# SparkFun_ProtoShield_Kit_rev32.net
KiCad netlist of a schematic drawn in EAGLE
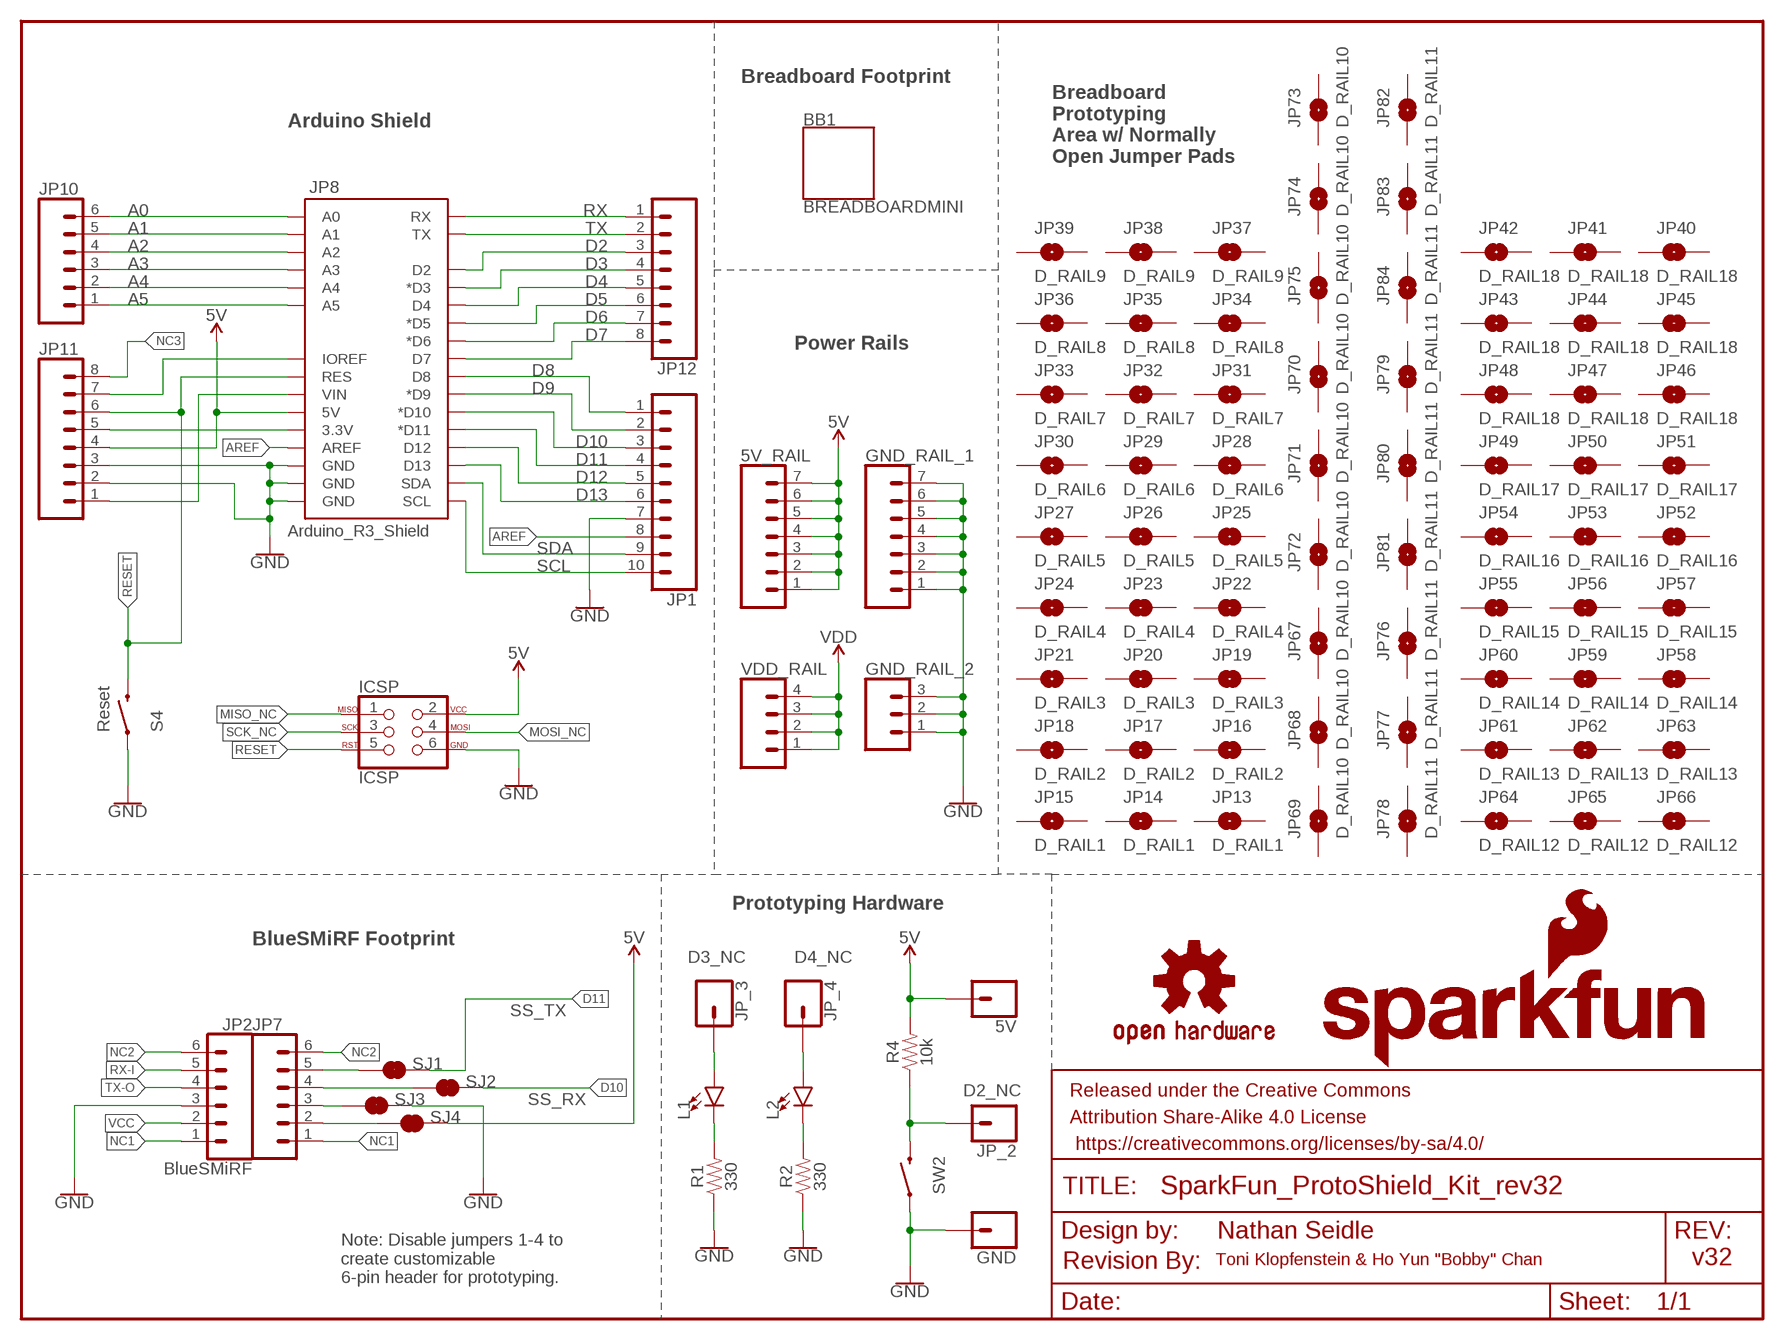
[diagram p0: schematic, sheet 1]

(export (version "E")
  (design (tool "Eeschema 10.0.6"))
  (components
    (comp (ref "5V")
      (value "CONN_01")
      (footprint "eagle-import:1X01")
      (libsource (lib "eagle-import") (part "CONN_01"))
    )
    (comp (ref "5V_RAIL")
      (value "CONN_07NO_SILK")
      (footprint "eagle-import:1X07_NO_SILK")
      (libsource (lib "eagle-import") (part "CONN_07NO_SILK"))
    )
    (comp (ref "BB1")
      (value "BREADBOARDMINI")
      (footprint "eagle-import:BREADBOARD-MINI")
      (libsource (lib "eagle-import") (part "BREADBOARDMINI"))
    )
    (comp (ref "FRAME1")
      (value "FRAME-LETTER")
      (footprint "eagle-import:CREATIVE_COMMONS")
      (libsource (lib "eagle-import") (part "FRAME-LETTER"))
    )
    (comp (ref "GND")
      (value "CONN_01")
      (footprint "eagle-import:1X01")
      (libsource (lib "eagle-import") (part "CONN_01"))
    )
    (comp (ref "GND_RAIL_1")
      (value "CONN_07NO_SILK")
      (footprint "eagle-import:1X07_NO_SILK")
      (libsource (lib "eagle-import") (part "CONN_07NO_SILK"))
    )
    (comp (ref "GND_RAIL_2")
      (value "CONN_031X03_NO_SILK")
      (footprint "eagle-import:1X03_NO_SILK")
      (libsource (lib "eagle-import") (part "CONN_031X03_NO_SILK"))
    )
    (comp (ref "ICSP")
      (value "ICSP")
      (footprint "eagle-import:2X3")
      (libsource (lib "eagle-import") (part "AVR_SPI_PROG_3X2PTH"))
    )
    (comp (ref "JP1")
      (value "CONN_10\"")
      (footprint "eagle-import:1X10")
      (libsource (lib "eagle-import") (part "CONN_10{dblquote}"))
    )
    (comp (ref "JP2")
      (value "BlueSMiRF")
      (footprint "eagle-import:1X06")
      (libsource (lib "eagle-import") (part "CONN_06SILK_FEMALE_PTH"))
    )
    (comp (ref "JP7")
      (value "CONN_06SILK_FEMALE_PTH")
      (footprint "eagle-import:1X06")
      (libsource (lib "eagle-import") (part "CONN_06SILK_FEMALE_PTH"))
    )
    (comp (ref "JP8")
      (value "ARDUINO_R3_SHIELDR3_PROTO_SHIELD")
      (footprint "eagle-import:UNO_R3_PROTO_SHIELD")
      (libsource (lib "eagle-import") (part "ARDUINO_R3_SHIELDR3_PROTO_SHIELD"))
    )
    (comp (ref "JP10")
      (value "CONN_06SILK_FEMALE_PTH")
      (footprint "eagle-import:1X06")
      (libsource (lib "eagle-import") (part "CONN_06SILK_FEMALE_PTH"))
    )
    (comp (ref "JP11")
      (value "CONN_08\"")
      (footprint "eagle-import:1X08")
      (libsource (lib "eagle-import") (part "CONN_08{dblquote}"))
    )
    (comp (ref "JP12")
      (value "CONN_08\"")
      (footprint "eagle-import:1X08")
      (libsource (lib "eagle-import") (part "CONN_08{dblquote}"))
    )
    (comp (ref "JP13")
      (value "D_RAIL1")
      (footprint "eagle-import:SMT-JUMPER_2_NO_NO-SILK")
      (libsource (lib "eagle-import") (part "JUMPER-SMT_2_NO_NO-SILK"))
    )
    (comp (ref "JP14")
      (value "D_RAIL1")
      (footprint "eagle-import:SMT-JUMPER_2_NO_NO-SILK")
      (libsource (lib "eagle-import") (part "JUMPER-SMT_2_NO_NO-SILK"))
    )
    (comp (ref "JP15")
      (value "D_RAIL1")
      (footprint "eagle-import:SMT-JUMPER_2_NO_NO-SILK")
      (libsource (lib "eagle-import") (part "JUMPER-SMT_2_NO_NO-SILK"))
    )
    (comp (ref "JP16")
      (value "D_RAIL2")
      (footprint "eagle-import:SMT-JUMPER_2_NO_NO-SILK")
      (libsource (lib "eagle-import") (part "JUMPER-SMT_2_NO_NO-SILK"))
    )
    (comp (ref "JP17")
      (value "D_RAIL2")
      (footprint "eagle-import:SMT-JUMPER_2_NO_NO-SILK")
      (libsource (lib "eagle-import") (part "JUMPER-SMT_2_NO_NO-SILK"))
    )
    (comp (ref "JP18")
      (value "D_RAIL2")
      (footprint "eagle-import:SMT-JUMPER_2_NO_NO-SILK")
      (libsource (lib "eagle-import") (part "JUMPER-SMT_2_NO_NO-SILK"))
    )
    (comp (ref "JP19")
      (value "D_RAIL3")
      (footprint "eagle-import:SMT-JUMPER_2_NO_NO-SILK")
      (libsource (lib "eagle-import") (part "JUMPER-SMT_2_NO_NO-SILK"))
    )
    (comp (ref "JP20")
      (value "D_RAIL3")
      (footprint "eagle-import:SMT-JUMPER_2_NO_NO-SILK")
      (libsource (lib "eagle-import") (part "JUMPER-SMT_2_NO_NO-SILK"))
    )
    (comp (ref "JP21")
      (value "D_RAIL3")
      (footprint "eagle-import:SMT-JUMPER_2_NO_NO-SILK")
      (libsource (lib "eagle-import") (part "JUMPER-SMT_2_NO_NO-SILK"))
    )
    (comp (ref "JP22")
      (value "D_RAIL4")
      (footprint "eagle-import:SMT-JUMPER_2_NO_NO-SILK")
      (libsource (lib "eagle-import") (part "JUMPER-SMT_2_NO_NO-SILK"))
    )
    (comp (ref "JP23")
      (value "D_RAIL4")
      (footprint "eagle-import:SMT-JUMPER_2_NO_NO-SILK")
      (libsource (lib "eagle-import") (part "JUMPER-SMT_2_NO_NO-SILK"))
    )
    (comp (ref "JP24")
      (value "D_RAIL4")
      (footprint "eagle-import:SMT-JUMPER_2_NO_NO-SILK")
      (libsource (lib "eagle-import") (part "JUMPER-SMT_2_NO_NO-SILK"))
    )
    (comp (ref "JP25")
      (value "D_RAIL5")
      (footprint "eagle-import:SMT-JUMPER_2_NO_NO-SILK")
      (libsource (lib "eagle-import") (part "JUMPER-SMT_2_NO_NO-SILK"))
    )
    (comp (ref "JP26")
      (value "D_RAIL5")
      (footprint "eagle-import:SMT-JUMPER_2_NO_NO-SILK")
      (libsource (lib "eagle-import") (part "JUMPER-SMT_2_NO_NO-SILK"))
    )
    (comp (ref "JP27")
      (value "D_RAIL5")
      (footprint "eagle-import:SMT-JUMPER_2_NO_NO-SILK")
      (libsource (lib "eagle-import") (part "JUMPER-SMT_2_NO_NO-SILK"))
    )
    (comp (ref "JP28")
      (value "D_RAIL6")
      (footprint "eagle-import:SMT-JUMPER_2_NO_NO-SILK")
      (libsource (lib "eagle-import") (part "JUMPER-SMT_2_NO_NO-SILK"))
    )
    (comp (ref "JP29")
      (value "D_RAIL6")
      (footprint "eagle-import:SMT-JUMPER_2_NO_NO-SILK")
      (libsource (lib "eagle-import") (part "JUMPER-SMT_2_NO_NO-SILK"))
    )
    (comp (ref "JP30")
      (value "D_RAIL6")
      (footprint "eagle-import:SMT-JUMPER_2_NO_NO-SILK")
      (libsource (lib "eagle-import") (part "JUMPER-SMT_2_NO_NO-SILK"))
    )
    (comp (ref "JP31")
      (value "D_RAIL7")
      (footprint "eagle-import:SMT-JUMPER_2_NO_NO-SILK")
      (libsource (lib "eagle-import") (part "JUMPER-SMT_2_NO_NO-SILK"))
    )
    (comp (ref "JP32")
      (value "D_RAIL7")
      (footprint "eagle-import:SMT-JUMPER_2_NO_NO-SILK")
      (libsource (lib "eagle-import") (part "JUMPER-SMT_2_NO_NO-SILK"))
    )
    (comp (ref "JP33")
      (value "D_RAIL7")
      (footprint "eagle-import:SMT-JUMPER_2_NO_NO-SILK")
      (libsource (lib "eagle-import") (part "JUMPER-SMT_2_NO_NO-SILK"))
    )
    (comp (ref "JP34")
      (value "D_RAIL8")
      (footprint "eagle-import:SMT-JUMPER_2_NO_NO-SILK")
      (libsource (lib "eagle-import") (part "JUMPER-SMT_2_NO_NO-SILK"))
    )
    (comp (ref "JP35")
      (value "D_RAIL8")
      (footprint "eagle-import:SMT-JUMPER_2_NO_NO-SILK")
      (libsource (lib "eagle-import") (part "JUMPER-SMT_2_NO_NO-SILK"))
    )
    (comp (ref "JP36")
      (value "D_RAIL8")
      (footprint "eagle-import:SMT-JUMPER_2_NO_NO-SILK")
      (libsource (lib "eagle-import") (part "JUMPER-SMT_2_NO_NO-SILK"))
    )
    (comp (ref "JP37")
      (value "D_RAIL9")
      (footprint "eagle-import:SMT-JUMPER_2_NO_NO-SILK")
      (libsource (lib "eagle-import") (part "JUMPER-SMT_2_NO_NO-SILK"))
    )
    (comp (ref "JP38")
      (value "D_RAIL9")
      (footprint "eagle-import:SMT-JUMPER_2_NO_NO-SILK")
      (libsource (lib "eagle-import") (part "JUMPER-SMT_2_NO_NO-SILK"))
    )
    (comp (ref "JP39")
      (value "D_RAIL9")
      (footprint "eagle-import:SMT-JUMPER_2_NO_NO-SILK")
      (libsource (lib "eagle-import") (part "JUMPER-SMT_2_NO_NO-SILK"))
    )
    (comp (ref "JP40")
      (value "D_RAIL18")
      (footprint "eagle-import:SMT-JUMPER_2_NO_NO-SILK")
      (libsource (lib "eagle-import") (part "JUMPER-SMT_2_NO_NO-SILK"))
    )
    (comp (ref "JP41")
      (value "D_RAIL18")
      (footprint "eagle-import:SMT-JUMPER_2_NO_NO-SILK")
      (libsource (lib "eagle-import") (part "JUMPER-SMT_2_NO_NO-SILK"))
    )
    (comp (ref "JP42")
      (value "D_RAIL18")
      (footprint "eagle-import:SMT-JUMPER_2_NO_NO-SILK")
      (libsource (lib "eagle-import") (part "JUMPER-SMT_2_NO_NO-SILK"))
    )
    (comp (ref "JP43")
      (value "D_RAIL18")
      (footprint "eagle-import:SMT-JUMPER_2_NO_NO-SILK")
      (libsource (lib "eagle-import") (part "JUMPER-SMT_2_NO_NO-SILK"))
    )
    (comp (ref "JP44")
      (value "D_RAIL18")
      (footprint "eagle-import:SMT-JUMPER_2_NO_NO-SILK")
      (libsource (lib "eagle-import") (part "JUMPER-SMT_2_NO_NO-SILK"))
    )
    (comp (ref "JP45")
      (value "D_RAIL18")
      (footprint "eagle-import:SMT-JUMPER_2_NO_NO-SILK")
      (libsource (lib "eagle-import") (part "JUMPER-SMT_2_NO_NO-SILK"))
    )
    (comp (ref "JP46")
      (value "D_RAIL18")
      (footprint "eagle-import:SMT-JUMPER_2_NO_NO-SILK")
      (libsource (lib "eagle-import") (part "JUMPER-SMT_2_NO_NO-SILK"))
    )
    (comp (ref "JP47")
      (value "D_RAIL18")
      (footprint "eagle-import:SMT-JUMPER_2_NO_NO-SILK")
      (libsource (lib "eagle-import") (part "JUMPER-SMT_2_NO_NO-SILK"))
    )
    (comp (ref "JP48")
      (value "D_RAIL18")
      (footprint "eagle-import:SMT-JUMPER_2_NO_NO-SILK")
      (libsource (lib "eagle-import") (part "JUMPER-SMT_2_NO_NO-SILK"))
    )
    (comp (ref "JP49")
      (value "D_RAIL17")
      (footprint "eagle-import:SMT-JUMPER_2_NO_NO-SILK")
      (libsource (lib "eagle-import") (part "JUMPER-SMT_2_NO_NO-SILK"))
    )
    (comp (ref "JP50")
      (value "D_RAIL17")
      (footprint "eagle-import:SMT-JUMPER_2_NO_NO-SILK")
      (libsource (lib "eagle-import") (part "JUMPER-SMT_2_NO_NO-SILK"))
    )
    (comp (ref "JP51")
      (value "D_RAIL17")
      (footprint "eagle-import:SMT-JUMPER_2_NO_NO-SILK")
      (libsource (lib "eagle-import") (part "JUMPER-SMT_2_NO_NO-SILK"))
    )
    (comp (ref "JP52")
      (value "D_RAIL16")
      (footprint "eagle-import:SMT-JUMPER_2_NO_NO-SILK")
      (libsource (lib "eagle-import") (part "JUMPER-SMT_2_NO_NO-SILK"))
    )
    (comp (ref "JP53")
      (value "D_RAIL16")
      (footprint "eagle-import:SMT-JUMPER_2_NO_NO-SILK")
      (libsource (lib "eagle-import") (part "JUMPER-SMT_2_NO_NO-SILK"))
    )
    (comp (ref "JP54")
      (value "D_RAIL16")
      (footprint "eagle-import:SMT-JUMPER_2_NO_NO-SILK")
      (libsource (lib "eagle-import") (part "JUMPER-SMT_2_NO_NO-SILK"))
    )
    (comp (ref "JP55")
      (value "D_RAIL15")
      (footprint "eagle-import:SMT-JUMPER_2_NO_NO-SILK")
      (libsource (lib "eagle-import") (part "JUMPER-SMT_2_NO_NO-SILK"))
    )
    (comp (ref "JP56")
      (value "D_RAIL15")
      (footprint "eagle-import:SMT-JUMPER_2_NO_NO-SILK")
      (libsource (lib "eagle-import") (part "JUMPER-SMT_2_NO_NO-SILK"))
    )
    (comp (ref "JP57")
      (value "D_RAIL15")
      (footprint "eagle-import:SMT-JUMPER_2_NO_NO-SILK")
      (libsource (lib "eagle-import") (part "JUMPER-SMT_2_NO_NO-SILK"))
    )
    (comp (ref "JP58")
      (value "D_RAIL14")
      (footprint "eagle-import:SMT-JUMPER_2_NO_NO-SILK")
      (libsource (lib "eagle-import") (part "JUMPER-SMT_2_NO_NO-SILK"))
    )
    (comp (ref "JP59")
      (value "D_RAIL14")
      (footprint "eagle-import:SMT-JUMPER_2_NO_NO-SILK")
      (libsource (lib "eagle-import") (part "JUMPER-SMT_2_NO_NO-SILK"))
    )
    (comp (ref "JP60")
      (value "D_RAIL14")
      (footprint "eagle-import:SMT-JUMPER_2_NO_NO-SILK")
      (libsource (lib "eagle-import") (part "JUMPER-SMT_2_NO_NO-SILK"))
    )
    (comp (ref "JP61")
      (value "D_RAIL13")
      (footprint "eagle-import:SMT-JUMPER_2_NO_NO-SILK")
      (libsource (lib "eagle-import") (part "JUMPER-SMT_2_NO_NO-SILK"))
    )
    (comp (ref "JP62")
      (value "D_RAIL13")
      (footprint "eagle-import:SMT-JUMPER_2_NO_NO-SILK")
      (libsource (lib "eagle-import") (part "JUMPER-SMT_2_NO_NO-SILK"))
    )
    (comp (ref "JP63")
      (value "D_RAIL13")
      (footprint "eagle-import:SMT-JUMPER_2_NO_NO-SILK")
      (libsource (lib "eagle-import") (part "JUMPER-SMT_2_NO_NO-SILK"))
    )
    (comp (ref "JP64")
      (value "D_RAIL12")
      (footprint "eagle-import:SMT-JUMPER_2_NO_NO-SILK")
      (libsource (lib "eagle-import") (part "JUMPER-SMT_2_NO_NO-SILK"))
    )
    (comp (ref "JP65")
      (value "D_RAIL12")
      (footprint "eagle-import:SMT-JUMPER_2_NO_NO-SILK")
      (libsource (lib "eagle-import") (part "JUMPER-SMT_2_NO_NO-SILK"))
    )
    (comp (ref "JP66")
      (value "D_RAIL12")
      (footprint "eagle-import:SMT-JUMPER_2_NO_NO-SILK")
      (libsource (lib "eagle-import") (part "JUMPER-SMT_2_NO_NO-SILK"))
    )
    (comp (ref "JP67")
      (value "D_RAIL10")
      (footprint "eagle-import:SMT-JUMPER_2_NO_NO-SILK")
      (libsource (lib "eagle-import") (part "JUMPER-SMT_2_NO_NO-SILK"))
    )
    (comp (ref "JP68")
      (value "D_RAIL10")
      (footprint "eagle-import:SMT-JUMPER_2_NO_NO-SILK")
      (libsource (lib "eagle-import") (part "JUMPER-SMT_2_NO_NO-SILK"))
    )
    (comp (ref "JP69")
      (value "D_RAIL10")
      (footprint "eagle-import:SMT-JUMPER_2_NO_NO-SILK")
      (libsource (lib "eagle-import") (part "JUMPER-SMT_2_NO_NO-SILK"))
    )
    (comp (ref "JP70")
      (value "D_RAIL10")
      (footprint "eagle-import:SMT-JUMPER_2_NO_NO-SILK")
      (libsource (lib "eagle-import") (part "JUMPER-SMT_2_NO_NO-SILK"))
    )
    (comp (ref "JP71")
      (value "D_RAIL10")
      (footprint "eagle-import:SMT-JUMPER_2_NO_NO-SILK")
      (libsource (lib "eagle-import") (part "JUMPER-SMT_2_NO_NO-SILK"))
    )
    (comp (ref "JP72")
      (value "D_RAIL10")
      (footprint "eagle-import:SMT-JUMPER_2_NO_NO-SILK")
      (libsource (lib "eagle-import") (part "JUMPER-SMT_2_NO_NO-SILK"))
    )
    (comp (ref "JP73")
      (value "D_RAIL10")
      (footprint "eagle-import:SMT-JUMPER_2_NO_NO-SILK")
      (libsource (lib "eagle-import") (part "JUMPER-SMT_2_NO_NO-SILK"))
    )
    (comp (ref "JP74")
      (value "D_RAIL10")
      (footprint "eagle-import:SMT-JUMPER_2_NO_NO-SILK")
      (libsource (lib "eagle-import") (part "JUMPER-SMT_2_NO_NO-SILK"))
    )
    (comp (ref "JP75")
      (value "D_RAIL10")
      (footprint "eagle-import:SMT-JUMPER_2_NO_NO-SILK")
      (libsource (lib "eagle-import") (part "JUMPER-SMT_2_NO_NO-SILK"))
    )
    (comp (ref "JP76")
      (value "D_RAIL11")
      (footprint "eagle-import:SMT-JUMPER_2_NO_NO-SILK")
      (libsource (lib "eagle-import") (part "JUMPER-SMT_2_NO_NO-SILK"))
    )
    (comp (ref "JP77")
      (value "D_RAIL11")
      (footprint "eagle-import:SMT-JUMPER_2_NO_NO-SILK")
      (libsource (lib "eagle-import") (part "JUMPER-SMT_2_NO_NO-SILK"))
    )
    (comp (ref "JP78")
      (value "D_RAIL11")
      (footprint "eagle-import:SMT-JUMPER_2_NO_NO-SILK")
      (libsource (lib "eagle-import") (part "JUMPER-SMT_2_NO_NO-SILK"))
    )
    (comp (ref "JP79")
      (value "D_RAIL11")
      (footprint "eagle-import:SMT-JUMPER_2_NO_NO-SILK")
      (libsource (lib "eagle-import") (part "JUMPER-SMT_2_NO_NO-SILK"))
    )
    (comp (ref "JP80")
      (value "D_RAIL11")
      (footprint "eagle-import:SMT-JUMPER_2_NO_NO-SILK")
      (libsource (lib "eagle-import") (part "JUMPER-SMT_2_NO_NO-SILK"))
    )
    (comp (ref "JP81")
      (value "D_RAIL11")
      (footprint "eagle-import:SMT-JUMPER_2_NO_NO-SILK")
      (libsource (lib "eagle-import") (part "JUMPER-SMT_2_NO_NO-SILK"))
    )
    (comp (ref "JP82")
      (value "D_RAIL11")
      (footprint "eagle-import:SMT-JUMPER_2_NO_NO-SILK")
      (libsource (lib "eagle-import") (part "JUMPER-SMT_2_NO_NO-SILK"))
    )
    (comp (ref "JP83")
      (value "D_RAIL11")
      (footprint "eagle-import:SMT-JUMPER_2_NO_NO-SILK")
      (libsource (lib "eagle-import") (part "JUMPER-SMT_2_NO_NO-SILK"))
    )
    (comp (ref "JP84")
      (value "D_RAIL11")
      (footprint "eagle-import:SMT-JUMPER_2_NO_NO-SILK")
      (libsource (lib "eagle-import") (part "JUMPER-SMT_2_NO_NO-SILK"))
    )
    (comp (ref "JP_2")
      (value "CONN_01")
      (footprint "eagle-import:1X01")
      (libsource (lib "eagle-import") (part "CONN_01"))
    )
    (comp (ref "JP_3")
      (value "CONN_01")
      (footprint "eagle-import:1X01")
      (libsource (lib "eagle-import") (part "CONN_01"))
    )
    (comp (ref "JP_4")
      (value "CONN_01")
      (footprint "eagle-import:1X01")
      (libsource (lib "eagle-import") (part "CONN_01"))
    )
    (comp (ref "L1")
      (value "LED3MM")
      (footprint "eagle-import:LED_3MM")
      (libsource (lib "eagle-import") (part "LED3MM"))
    )
    (comp (ref "L2")
      (value "LED3MM")
      (footprint "eagle-import:LED_3MM")
      (libsource (lib "eagle-import") (part "LED3MM"))
    )
    (comp (ref "LOGO1")
      (value "OSHW-LOGOS")
      (footprint "eagle-import:OSHW-LOGO-S")
      (libsource (lib "eagle-import") (part "OSHW-LOGOS"))
    )
    (comp (ref "R1")
      (value "330")
      (footprint "eagle-import:AXIAL-0.3")
      (libsource (lib "eagle-import") (part "330OHM-HORIZ-1/10W-5%"))
    )
    (comp (ref "R2")
      (value "330")
      (footprint "eagle-import:AXIAL-0.3")
      (libsource (lib "eagle-import") (part "330OHM-HORIZ-1/10W-5%"))
    )
    (comp (ref "R4")
      (value "10k")
      (footprint "eagle-import:AXIAL-0.3")
      (libsource (lib "eagle-import") (part "10KOHM-HORIZ-1/4W-5%"))
    )
    (comp (ref "S4")
      (value "MOMENTARY-SWITCH-SPST-PTH-6.0MM")
      (footprint "eagle-import:TACTILE_SWITCH_PTH_6.0MM")
      (libsource (lib "eagle-import") (part "MOMENTARY-SWITCH-SPST-PTH-6.0MM"))
    )
    (comp (ref "SJ1")
      (value "JUMPER-SMT_2_NC_TRACE_SILK")
      (footprint "eagle-import:SMT-JUMPER_2_NC_TRACE_SILK")
      (libsource (lib "eagle-import") (part "JUMPER-SMT_2_NC_TRACE_SILK"))
    )
    (comp (ref "SJ2")
      (value "JUMPER-SMT_2_NC_TRACE_SILK")
      (footprint "eagle-import:SMT-JUMPER_2_NC_TRACE_SILK")
      (libsource (lib "eagle-import") (part "JUMPER-SMT_2_NC_TRACE_SILK"))
    )
    (comp (ref "SJ3")
      (value "JUMPER-SMT_2_NC_TRACE_SILK")
      (footprint "eagle-import:SMT-JUMPER_2_NC_TRACE_SILK")
      (libsource (lib "eagle-import") (part "JUMPER-SMT_2_NC_TRACE_SILK"))
    )
    (comp (ref "SJ4")
      (value "JUMPER-SMT_2_NC_TRACE_SILK")
      (footprint "eagle-import:SMT-JUMPER_2_NC_TRACE_SILK")
      (libsource (lib "eagle-import") (part "JUMPER-SMT_2_NC_TRACE_SILK"))
    )
    (comp (ref "SW2")
      (value "MOMENTARY-SWITCH-SPST-PTH-6.0MM")
      (footprint "eagle-import:TACTILE_SWITCH_PTH_6.0MM")
      (libsource (lib "eagle-import") (part "MOMENTARY-SWITCH-SPST-PTH-6.0MM"))
    )
    (comp (ref "U$1")
      (value "SFE_LOGO_NAME_FLAME.1_INCH")
      (footprint "eagle-import:SFE_LOGO_NAME_FLAME_.1")
      (libsource (lib "eagle-import") (part "SFE_LOGO_NAME_FLAME.1_INCH"))
    )
    (comp (ref "U$2")
      (value "REVISION")
      (footprint "eagle-import:REVISION")
      (libsource (lib "eagle-import") (part "REVISION"))
    )
    (comp (ref "VDD_RAIL")
      (value "CONN_041X04_NO_SILK")
      (footprint "eagle-import:1X04_NO_SILK")
      (libsource (lib "eagle-import") (part "CONN_041X04_NO_SILK"))
    )
  )
  (nets
    (net (code "1") (name "/D2") (class "Default")
      (node (ref "JP12") (pin "3") (pinfunction "3_3") (pintype "passive"))
      (node (ref "JP8") (pin "D2") (pinfunction "D2_D2") (pintype "bidirectional"))
    )
    (net (code "2") (name "/D2_NC") (class "Default")
      (node (ref "JP_2") (pin "1") (pinfunction "1_1") (pintype "passive"))
      (node (ref "R4") (pin "P$1") (pinfunction "1_P$1") (pintype "passive"))
      (node (ref "SW2") (pin "3") (pinfunction "2_3") (pintype "passive"))
    )
    (net (code "3") (name "/D3") (class "Default")
      (node (ref "JP12") (pin "4") (pinfunction "4_4") (pintype "passive"))
      (node (ref "JP8") (pin "D3") (pinfunction "*D3_D3") (pintype "bidirectional"))
    )
    (net (code "4") (name "/D4") (class "Default")
      (node (ref "JP12") (pin "5") (pinfunction "5_5") (pintype "passive"))
      (node (ref "JP8") (pin "D4") (pinfunction "D4_D4") (pintype "bidirectional"))
    )
    (net (code "5") (name "/D5") (class "Default")
      (node (ref "JP12") (pin "6") (pinfunction "6_6") (pintype "passive"))
      (node (ref "JP8") (pin "D5") (pinfunction "*D5_D5") (pintype "bidirectional"))
    )
    (net (code "6") (name "/D6") (class "Default")
      (node (ref "JP12") (pin "7") (pinfunction "7_7") (pintype "passive"))
      (node (ref "JP8") (pin "D6") (pinfunction "*D6_D6") (pintype "bidirectional"))
    )
    (net (code "7") (name "/D7") (class "Default")
      (node (ref "JP12") (pin "8") (pinfunction "8_8") (pintype "passive"))
      (node (ref "JP8") (pin "D7") (pinfunction "D7_D7") (pintype "bidirectional"))
    )
    (net (code "8") (name "/D8") (class "Default")
      (node (ref "JP1") (pin "1") (pinfunction "1_1") (pintype "passive"))
      (node (ref "JP8") (pin "D8") (pinfunction "D8_D8") (pintype "bidirectional"))
    )
    (net (code "9") (name "/D9") (class "Default")
      (node (ref "JP1") (pin "2") (pinfunction "2_2") (pintype "passive"))
      (node (ref "JP8") (pin "D9") (pinfunction "*D9_D9") (pintype "bidirectional"))
    )
    (net (code "10") (name "/D12") (class "Default")
      (node (ref "JP1") (pin "5") (pinfunction "5_5") (pintype "passive"))
      (node (ref "JP8") (pin "D12") (pinfunction "D12_D12") (pintype "bidirectional"))
    )
    (net (code "11") (name "/D13") (class "Default")
      (node (ref "JP1") (pin "6") (pinfunction "6_6") (pintype "passive"))
      (node (ref "JP8") (pin "D13") (pinfunction "D13_D13") (pintype "bidirectional"))
    )
    (net (code "12") (name "/RX") (class "Default")
      (node (ref "JP12") (pin "1") (pinfunction "1_1") (pintype "passive"))
      (node (ref "JP8") (pin "RX") (pinfunction "RX_RX") (pintype "bidirectional"))
    )
    (net (code "13") (name "/SCL") (class "Default")
      (node (ref "JP1") (pin "10") (pinfunction "10_10") (pintype "passive"))
      (node (ref "JP8") (pin "SCL") (pinfunction "SCL_SCL") (pintype "bidirectional"))
    )
    (net (code "14") (name "/SDA") (class "Default")
      (node (ref "JP1") (pin "9") (pinfunction "9_9") (pintype "passive"))
      (node (ref "JP8") (pin "SDA") (pinfunction "SDA_SDA") (pintype "bidirectional"))
    )
    (net (code "15") (name "/TX") (class "Default")
      (node (ref "JP12") (pin "2") (pinfunction "2_2") (pintype "passive"))
      (node (ref "JP8") (pin "TX") (pinfunction "TX_TX") (pintype "bidirectional"))
    )
    (net (code "16") (name "5V") (class "Default")
      (node (ref "5V") (pin "1") (pinfunction "1_1") (pintype "passive"))
      (node (ref "5V_RAIL") (pin "1") (pinfunction "1_1") (pintype "passive"))
      (node (ref "5V_RAIL") (pin "2") (pinfunction "2_2") (pintype "passive"))
      (node (ref "5V_RAIL") (pin "3") (pinfunction "3_3") (pintype "passive"))
      (node (ref "5V_RAIL") (pin "4") (pinfunction "4_4") (pintype "passive"))
      (node (ref "5V_RAIL") (pin "5") (pinfunction "5_5") (pintype "passive"))
      (node (ref "5V_RAIL") (pin "6") (pinfunction "6_6") (pintype "passive"))
      (node (ref "5V_RAIL") (pin "7") (pinfunction "7_7") (pintype "passive"))
      (node (ref "ICSP") (pin "2") (pinfunction "2_2") (pintype "passive"))
      (node (ref "JP11") (pin "4") (pinfunction "4_4") (pintype "passive"))
      (node (ref "JP8") (pin "5V") (pinfunction "5V_5V") (pintype "bidirectional"))
      (node (ref "R4") (pin "P$2") (pinfunction "2_P$2") (pintype "passive"))
      (node (ref "SJ4") (pin "2") (pinfunction "2_2") (pintype "passive"))
    )
    (net (code "17") (name "AREF") (class "Default")
      (node (ref "JP1") (pin "8") (pinfunction "8_8") (pintype "passive"))
      (node (ref "JP8") (pin "AREF") (pinfunction "AREF_AREF") (pintype "bidirectional"))
    )
    (net (code "18") (name "D10") (class "Default")
      (node (ref "JP1") (pin "3") (pinfunction "3_3") (pintype "passive"))
      (node (ref "JP8") (pin "D10") (pinfunction "*D10_D10") (pintype "bidirectional"))
      (node (ref "SJ2") (pin "2") (pinfunction "2_2") (pintype "passive"))
    )
    (net (code "19") (name "D11") (class "Default")
      (node (ref "JP1") (pin "4") (pinfunction "4_4") (pintype "passive"))
      (node (ref "JP8") (pin "D11") (pinfunction "*D11_D11") (pintype "bidirectional"))
      (node (ref "SJ1") (pin "2") (pinfunction "2_2") (pintype "passive"))
    )
    (net (code "20") (name "GND") (class "Default")
      (node (ref "GND") (pin "1") (pinfunction "1_1") (pintype "passive"))
      (node (ref "GND_RAIL_1") (pin "1") (pinfunction "1_1") (pintype "passive"))
      (node (ref "GND_RAIL_1") (pin "2") (pinfunction "2_2") (pintype "passive"))
      (node (ref "GND_RAIL_1") (pin "3") (pinfunction "3_3") (pintype "passive"))
      (node (ref "GND_RAIL_1") (pin "4") (pinfunction "4_4") (pintype "passive"))
      (node (ref "GND_RAIL_1") (pin "5") (pinfunction "5_5") (pintype "passive"))
      (node (ref "GND_RAIL_1") (pin "6") (pinfunction "6_6") (pintype "passive"))
      (node (ref "GND_RAIL_1") (pin "7") (pinfunction "7_7") (pintype "passive"))
      (node (ref "GND_RAIL_2") (pin "1") (pinfunction "1_1") (pintype "passive"))
      (node (ref "GND_RAIL_2") (pin "2") (pinfunction "2_2") (pintype "passive"))
      (node (ref "GND_RAIL_2") (pin "3") (pinfunction "3_3") (pintype "passive"))
      (node (ref "ICSP") (pin "6") (pinfunction "6_6") (pintype "passive"))
      (node (ref "JP1") (pin "7") (pinfunction "7_7") (pintype "passive"))
      (node (ref "JP11") (pin "2") (pinfunction "2_2") (pintype "passive"))
      (node (ref "JP11") (pin "3") (pinfunction "3_3") (pintype "passive"))
      (node (ref "JP2") (pin "3") (pinfunction "3_3") (pintype "passive"))
      (node (ref "JP7") (pin "3") (pinfunction "3_3") (pintype "passive"))
      (node (ref "JP8") (pin "GND@0") (pinfunction "GND_GND@0") (pintype "bidirectional"))
      (node (ref "JP8") (pin "GND@1") (pinfunction "GND_GND@1") (pintype "bidirectional"))
      (node (ref "JP8") (pin "GND@2") (pinfunction "GND_GND@2") (pintype "bidirectional"))
      (node (ref "R1") (pin "P$1") (pinfunction "1_P$1") (pintype "passive"))
      (node (ref "R2") (pin "P$1") (pinfunction "1_P$1") (pintype "passive"))
      (node (ref "S4") (pin "1") (pinfunction "1_1") (pintype "passive"))
      (node (ref "SJ3") (pin "1") (pinfunction "1_1") (pintype "passive"))
      (node (ref "SJ3") (pin "2") (pinfunction "2_2") (pintype "passive"))
      (node (ref "SW2") (pin "1") (pinfunction "1_1") (pintype "passive"))
    )
    (net (code "21") (name "MISO_NC") (class "Default")
      (node (ref "ICSP") (pin "1") (pinfunction "1_1") (pintype "passive"))
    )
    (net (code "22") (name "MOSI_NC") (class "Default")
      (node (ref "ICSP") (pin "4") (pinfunction "4_4") (pintype "passive"))
    )
    (net (code "23") (name "NC1") (class "Default")
      (node (ref "JP2") (pin "1") (pinfunction "1_1") (pintype "passive"))
      (node (ref "JP7") (pin "1") (pinfunction "1_1") (pintype "passive"))
    )
    (net (code "24") (name "NC2") (class "Default")
      (node (ref "JP2") (pin "6") (pinfunction "6_6") (pintype "passive"))
      (node (ref "JP7") (pin "6") (pinfunction "6_6") (pintype "passive"))
    )
    (net (code "25") (name "NC3") (class "Default")
      (node (ref "JP11") (pin "8") (pinfunction "8_8") (pintype "passive"))
    )
    (net (code "26") (name "Net-(JP10-Pad1)") (class "Default")
      (node (ref "JP10") (pin "1") (pinfunction "1_1") (pintype "passive"))
      (node (ref "JP8") (pin "A5") (pinfunction "A5_A5") (pintype "bidirectional"))
    )
    (net (code "27") (name "Net-(JP10-Pad2)") (class "Default")
      (node (ref "JP10") (pin "2") (pinfunction "2_2") (pintype "passive"))
      (node (ref "JP8") (pin "A4") (pinfunction "A4_A4") (pintype "bidirectional"))
    )
    (net (code "28") (name "Net-(JP10-Pad3)") (class "Default")
      (node (ref "JP10") (pin "3") (pinfunction "3_3") (pintype "passive"))
      (node (ref "JP8") (pin "A3") (pinfunction "A3_A3") (pintype "bidirectional"))
    )
    (net (code "29") (name "Net-(JP10-Pad4)") (class "Default")
      (node (ref "JP10") (pin "4") (pinfunction "4_4") (pintype "passive"))
      (node (ref "JP8") (pin "A2") (pinfunction "A2_A2") (pintype "bidirectional"))
    )
    (net (code "30") (name "Net-(JP10-Pad5)") (class "Default")
      (node (ref "JP10") (pin "5") (pinfunction "5_5") (pintype "passive"))
      (node (ref "JP8") (pin "A1") (pinfunction "A1_A1") (pintype "bidirectional"))
    )
    (net (code "31") (name "Net-(JP10-Pad6)") (class "Default")
      (node (ref "JP10") (pin "6") (pinfunction "6_6") (pintype "passive"))
      (node (ref "JP8") (pin "A0") (pinfunction "A0_A0") (pintype "bidirectional"))
    )
    (net (code "32") (name "Net-(JP11-Pad1)") (class "Default")
      (node (ref "JP11") (pin "1") (pinfunction "1_1") (pintype "passive"))
      (node (ref "JP8") (pin "VIN") (pinfunction "VIN_VIN") (pintype "bidirectional"))
    )
    (net (code "33") (name "Net-(JP11-Pad5)") (class "Default")
      (node (ref "JP11") (pin "5") (pinfunction "5_5") (pintype "passive"))
      (node (ref "JP8") (pin "3.3V") (pinfunction "3.3V_3.3V") (pintype "bidirectional"))
    )
    (net (code "34") (name "Net-(JP11-Pad7)") (class "Default")
      (node (ref "JP11") (pin "7") (pinfunction "7_7") (pintype "passive"))
      (node (ref "JP8") (pin "IOREF") (pinfunction "IOREF_IOREF") (pintype "bidirectional"))
    )
    (net (code "35") (name "Net-(JP_3-Pad1)") (class "Default")
      (node (ref "JP_3") (pin "1") (pinfunction "1_1") (pintype "passive"))
      (node (ref "L1") (pin "A") (pinfunction "A_A") (pintype "passive"))
    )
    (net (code "36") (name "Net-(JP_4-Pad1)") (class "Default")
      (node (ref "JP_4") (pin "1") (pinfunction "1_1") (pintype "passive"))
      (node (ref "L2") (pin "A") (pinfunction "A_A") (pintype "passive"))
    )
    (net (code "37") (name "Net-(L1-C)") (class "Default")
      (node (ref "L1") (pin "K") (pinfunction "C_K") (pintype "passive"))
      (node (ref "R1") (pin "P$2") (pinfunction "2_P$2") (pintype "passive"))
    )
    (net (code "38") (name "Net-(L2-C)") (class "Default")
      (node (ref "L2") (pin "K") (pinfunction "C_K") (pintype "passive"))
      (node (ref "R2") (pin "P$2") (pinfunction "2_P$2") (pintype "passive"))
    )
    (net (code "39") (name "RESET") (class "Default")
      (node (ref "ICSP") (pin "5") (pinfunction "5_5") (pintype "passive"))
      (node (ref "JP11") (pin "6") (pinfunction "6_6") (pintype "passive"))
      (node (ref "JP8") (pin "RES") (pinfunction "RES_RES") (pintype "bidirectional"))
      (node (ref "S4") (pin "3") (pinfunction "2_3") (pintype "passive"))
    )
    (net (code "40") (name "RX-I") (class "Default")
      (node (ref "JP2") (pin "5") (pinfunction "5_5") (pintype "passive"))
      (node (ref "JP7") (pin "5") (pinfunction "5_5") (pintype "passive"))
      (node (ref "SJ1") (pin "1") (pinfunction "1_1") (pintype "passive"))
    )
    (net (code "41") (name "SCK_NC") (class "Default")
      (node (ref "ICSP") (pin "3") (pinfunction "3_3") (pintype "passive"))
    )
    (net (code "42") (name "TX-O") (class "Default")
      (node (ref "JP2") (pin "4") (pinfunction "4_4") (pintype "passive"))
      (node (ref "JP7") (pin "4") (pinfunction "4_4") (pintype "passive"))
      (node (ref "SJ2") (pin "1") (pinfunction "1_1") (pintype "passive"))
    )
    (net (code "43") (name "VCC") (class "Default")
      (node (ref "JP2") (pin "2") (pinfunction "2_2") (pintype "passive"))
      (node (ref "JP7") (pin "2") (pinfunction "2_2") (pintype "passive"))
      (node (ref "SJ4") (pin "1") (pinfunction "1_1") (pintype "passive"))
    )
    (net (code "44") (name "VDD") (class "Default")
      (node (ref "VDD_RAIL") (pin "1") (pinfunction "1_1") (pintype "passive"))
      (node (ref "VDD_RAIL") (pin "2") (pinfunction "2_2") (pintype "passive"))
      (node (ref "VDD_RAIL") (pin "3") (pinfunction "3_3") (pintype "passive"))
      (node (ref "VDD_RAIL") (pin "4") (pinfunction "4_4") (pintype "passive"))
    )
    (net (code "45") (name "unconnected-(JP13-Pad1)") (class "Default")
      (node (ref "JP13") (pin "1") (pinfunction "1_1") (pintype "passive"))
    )
    (net (code "46") (name "unconnected-(JP13-Pad2)") (class "Default")
      (node (ref "JP13") (pin "2") (pinfunction "2_2") (pintype "passive"))
    )
    (net (code "47") (name "unconnected-(JP14-Pad1)") (class "Default")
      (node (ref "JP14") (pin "1") (pinfunction "1_1") (pintype "passive"))
    )
    (net (code "48") (name "unconnected-(JP14-Pad2)") (class "Default")
      (node (ref "JP14") (pin "2") (pinfunction "2_2") (pintype "passive"))
    )
    (net (code "49") (name "unconnected-(JP15-Pad1)") (class "Default")
      (node (ref "JP15") (pin "1") (pinfunction "1_1") (pintype "passive"))
    )
    (net (code "50") (name "unconnected-(JP15-Pad2)") (class "Default")
      (node (ref "JP15") (pin "2") (pinfunction "2_2") (pintype "passive"))
    )
    (net (code "51") (name "unconnected-(JP16-Pad1)") (class "Default")
      (node (ref "JP16") (pin "1") (pinfunction "1_1") (pintype "passive"))
    )
    (net (code "52") (name "unconnected-(JP16-Pad2)") (class "Default")
      (node (ref "JP16") (pin "2") (pinfunction "2_2") (pintype "passive"))
    )
    (net (code "53") (name "unconnected-(JP17-Pad1)") (class "Default")
      (node (ref "JP17") (pin "1") (pinfunction "1_1") (pintype "passive"))
    )
    (net (code "54") (name "unconnected-(JP17-Pad2)") (class "Default")
      (node (ref "JP17") (pin "2") (pinfunction "2_2") (pintype "passive"))
    )
    (net (code "55") (name "unconnected-(JP18-Pad1)") (class "Default")
      (node (ref "JP18") (pin "1") (pinfunction "1_1") (pintype "passive"))
    )
    (net (code "56") (name "unconnected-(JP18-Pad2)") (class "Default")
      (node (ref "JP18") (pin "2") (pinfunction "2_2") (pintype "passive"))
    )
    (net (code "57") (name "unconnected-(JP19-Pad1)") (class "Default")
      (node (ref "JP19") (pin "1") (pinfunction "1_1") (pintype "passive"))
    )
    (net (code "58") (name "unconnected-(JP19-Pad2)") (class "Default")
      (node (ref "JP19") (pin "2") (pinfunction "2_2") (pintype "passive"))
    )
    (net (code "59") (name "unconnected-(JP20-Pad1)") (class "Default")
      (node (ref "JP20") (pin "1") (pinfunction "1_1") (pintype "passive"))
    )
    (net (code "60") (name "unconnected-(JP20-Pad2)") (class "Default")
      (node (ref "JP20") (pin "2") (pinfunction "2_2") (pintype "passive"))
    )
    (net (code "61") (name "unconnected-(JP21-Pad1)") (class "Default")
      (node (ref "JP21") (pin "1") (pinfunction "1_1") (pintype "passive"))
    )
    (net (code "62") (name "unconnected-(JP21-Pad2)") (class "Default")
      (node (ref "JP21") (pin "2") (pinfunction "2_2") (pintype "passive"))
    )
    (net (code "63") (name "unconnected-(JP22-Pad1)") (class "Default")
      (node (ref "JP22") (pin "1") (pinfunction "1_1") (pintype "passive"))
    )
    (net (code "64") (name "unconnected-(JP22-Pad2)") (class "Default")
      (node (ref "JP22") (pin "2") (pinfunction "2_2") (pintype "passive"))
    )
    (net (code "65") (name "unconnected-(JP23-Pad1)") (class "Default")
      (node (ref "JP23") (pin "1") (pinfunction "1_1") (pintype "passive"))
    )
    (net (code "66") (name "unconnected-(JP23-Pad2)") (class "Default")
      (node (ref "JP23") (pin "2") (pinfunction "2_2") (pintype "passive"))
    )
    (net (code "67") (name "unconnected-(JP24-Pad1)") (class "Default")
      (node (ref "JP24") (pin "1") (pinfunction "1_1") (pintype "passive"))
    )
    (net (code "68") (name "unconnected-(JP24-Pad2)") (class "Default")
      (node (ref "JP24") (pin "2") (pinfunction "2_2") (pintype "passive"))
    )
    (net (code "69") (name "unconnected-(JP25-Pad1)") (class "Default")
      (node (ref "JP25") (pin "1") (pinfunction "1_1") (pintype "passive"))
    )
    (net (code "70") (name "unconnected-(JP25-Pad2)") (class "Default")
      (node (ref "JP25") (pin "2") (pinfunction "2_2") (pintype "passive"))
    )
    (net (code "71") (name "unconnected-(JP26-Pad1)") (class "Default")
      (node (ref "JP26") (pin "1") (pinfunction "1_1") (pintype "passive"))
    )
    (net (code "72") (name "unconnected-(JP26-Pad2)") (class "Default")
      (node (ref "JP26") (pin "2") (pinfunction "2_2") (pintype "passive"))
    )
    (net (code "73") (name "unconnected-(JP27-Pad1)") (class "Default")
      (node (ref "JP27") (pin "1") (pinfunction "1_1") (pintype "passive"))
    )
    (net (code "74") (name "unconnected-(JP27-Pad2)") (class "Default")
      (node (ref "JP27") (pin "2") (pinfunction "2_2") (pintype "passive"))
    )
    (net (code "75") (name "unconnected-(JP28-Pad1)") (class "Default")
      (node (ref "JP28") (pin "1") (pinfunction "1_1") (pintype "passive"))
    )
    (net (code "76") (name "unconnected-(JP28-Pad2)") (class "Default")
      (node (ref "JP28") (pin "2") (pinfunction "2_2") (pintype "passive"))
    )
    (net (code "77") (name "unconnected-(JP29-Pad1)") (class "Default")
      (node (ref "JP29") (pin "1") (pinfunction "1_1") (pintype "passive"))
    )
    (net (code "78") (name "unconnected-(JP29-Pad2)") (class "Default")
      (node (ref "JP29") (pin "2") (pinfunction "2_2") (pintype "passive"))
    )
    (net (code "79") (name "unconnected-(JP30-Pad1)") (class "Default")
      (node (ref "JP30") (pin "1") (pinfunction "1_1") (pintype "passive"))
    )
    (net (code "80") (name "unconnected-(JP30-Pad2)") (class "Default")
      (node (ref "JP30") (pin "2") (pinfunction "2_2") (pintype "passive"))
    )
    (net (code "81") (name "unconnected-(JP31-Pad1)") (class "Default")
      (node (ref "JP31") (pin "1") (pinfunction "1_1") (pintype "passive"))
    )
    (net (code "82") (name "unconnected-(JP31-Pad2)") (class "Default")
      (node (ref "JP31") (pin "2") (pinfunction "2_2") (pintype "passive"))
    )
    (net (code "83") (name "unconnected-(JP32-Pad1)") (class "Default")
      (node (ref "JP32") (pin "1") (pinfunction "1_1") (pintype "passive"))
    )
    (net (code "84") (name "unconnected-(JP32-Pad2)") (class "Default")
      (node (ref "JP32") (pin "2") (pinfunction "2_2") (pintype "passive"))
    )
    (net (code "85") (name "unconnected-(JP33-Pad1)") (class "Default")
      (node (ref "JP33") (pin "1") (pinfunction "1_1") (pintype "passive"))
    )
    (net (code "86") (name "unconnected-(JP33-Pad2)") (class "Default")
      (node (ref "JP33") (pin "2") (pinfunction "2_2") (pintype "passive"))
    )
    (net (code "87") (name "unconnected-(JP34-Pad1)") (class "Default")
      (node (ref "JP34") (pin "1") (pinfunction "1_1") (pintype "passive"))
    )
    (net (code "88") (name "unconnected-(JP34-Pad2)") (class "Default")
      (node (ref "JP34") (pin "2") (pinfunction "2_2") (pintype "passive"))
    )
    (net (code "89") (name "unconnected-(JP35-Pad1)") (class "Default")
      (node (ref "JP35") (pin "1") (pinfunction "1_1") (pintype "passive"))
    )
    (net (code "90") (name "unconnected-(JP35-Pad2)") (class "Default")
      (node (ref "JP35") (pin "2") (pinfunction "2_2") (pintype "passive"))
    )
    (net (code "91") (name "unconnected-(JP36-Pad1)") (class "Default")
      (node (ref "JP36") (pin "1") (pinfunction "1_1") (pintype "passive"))
    )
    (net (code "92") (name "unconnected-(JP36-Pad2)") (class "Default")
      (node (ref "JP36") (pin "2") (pinfunction "2_2") (pintype "passive"))
    )
    (net (code "93") (name "unconnected-(JP37-Pad1)") (class "Default")
      (node (ref "JP37") (pin "1") (pinfunction "1_1") (pintype "passive"))
    )
    (net (code "94") (name "unconnected-(JP37-Pad2)") (class "Default")
      (node (ref "JP37") (pin "2") (pinfunction "2_2") (pintype "passive"))
    )
    (net (code "95") (name "unconnected-(JP38-Pad1)") (class "Default")
      (node (ref "JP38") (pin "1") (pinfunction "1_1") (pintype "passive"))
    )
    (net (code "96") (name "unconnected-(JP38-Pad2)") (class "Default")
      (node (ref "JP38") (pin "2") (pinfunction "2_2") (pintype "passive"))
    )
    (net (code "97") (name "unconnected-(JP39-Pad1)") (class "Default")
      (node (ref "JP39") (pin "1") (pinfunction "1_1") (pintype "passive"))
    )
    (net (code "98") (name "unconnected-(JP39-Pad2)") (class "Default")
      (node (ref "JP39") (pin "2") (pinfunction "2_2") (pintype "passive"))
    )
    (net (code "99") (name "unconnected-(JP40-Pad1)") (class "Default")
      (node (ref "JP40") (pin "1") (pinfunction "1_1") (pintype "passive"))
    )
    (net (code "100") (name "unconnected-(JP40-Pad2)") (class "Default")
      (node (ref "JP40") (pin "2") (pinfunction "2_2") (pintype "passive"))
    )
    (net (code "101") (name "unconnected-(JP41-Pad1)") (class "Default")
      (node (ref "JP41") (pin "1") (pinfunction "1_1") (pintype "passive"))
    )
    (net (code "102") (name "unconnected-(JP41-Pad2)") (class "Default")
      (node (ref "JP41") (pin "2") (pinfunction "2_2") (pintype "passive"))
    )
    (net (code "103") (name "unconnected-(JP42-Pad1)") (class "Default")
      (node (ref "JP42") (pin "1") (pinfunction "1_1") (pintype "passive"))
    )
    (net (code "104") (name "unconnected-(JP42-Pad2)") (class "Default")
      (node (ref "JP42") (pin "2") (pinfunction "2_2") (pintype "passive"))
    )
    (net (code "105") (name "unconnected-(JP43-Pad1)") (class "Default")
      (node (ref "JP43") (pin "1") (pinfunction "1_1") (pintype "passive"))
    )
    (net (code "106") (name "unconnected-(JP43-Pad2)") (class "Default")
      (node (ref "JP43") (pin "2") (pinfunction "2_2") (pintype "passive"))
    )
    (net (code "107") (name "unconnected-(JP44-Pad1)") (class "Default")
      (node (ref "JP44") (pin "1") (pinfunction "1_1") (pintype "passive"))
    )
    (net (code "108") (name "unconnected-(JP44-Pad2)") (class "Default")
      (node (ref "JP44") (pin "2") (pinfunction "2_2") (pintype "passive"))
    )
    (net (code "109") (name "unconnected-(JP45-Pad1)") (class "Default")
      (node (ref "JP45") (pin "1") (pinfunction "1_1") (pintype "passive"))
    )
    (net (code "110") (name "unconnected-(JP45-Pad2)") (class "Default")
      (node (ref "JP45") (pin "2") (pinfunction "2_2") (pintype "passive"))
    )
    (net (code "111") (name "unconnected-(JP46-Pad1)") (class "Default")
      (node (ref "JP46") (pin "1") (pinfunction "1_1") (pintype "passive"))
    )
    (net (code "112") (name "unconnected-(JP46-Pad2)") (class "Default")
      (node (ref "JP46") (pin "2") (pinfunction "2_2") (pintype "passive"))
    )
    (net (code "113") (name "unconnected-(JP47-Pad1)") (class "Default")
      (node (ref "JP47") (pin "1") (pinfunction "1_1") (pintype "passive"))
    )
    (net (code "114") (name "unconnected-(JP47-Pad2)") (class "Default")
      (node (ref "JP47") (pin "2") (pinfunction "2_2") (pintype "passive"))
    )
    (net (code "115") (name "unconnected-(JP48-Pad1)") (class "Default")
      (node (ref "JP48") (pin "1") (pinfunction "1_1") (pintype "passive"))
    )
    (net (code "116") (name "unconnected-(JP48-Pad2)") (class "Default")
      (node (ref "JP48") (pin "2") (pinfunction "2_2") (pintype "passive"))
    )
    (net (code "117") (name "unconnected-(JP49-Pad1)") (class "Default")
      (node (ref "JP49") (pin "1") (pinfunction "1_1") (pintype "passive"))
    )
    (net (code "118") (name "unconnected-(JP49-Pad2)") (class "Default")
      (node (ref "JP49") (pin "2") (pinfunction "2_2") (pintype "passive"))
    )
    (net (code "119") (name "unconnected-(JP50-Pad1)") (class "Default")
      (node (ref "JP50") (pin "1") (pinfunction "1_1") (pintype "passive"))
    )
    (net (code "120") (name "unconnected-(JP50-Pad2)") (class "Default")
      (node (ref "JP50") (pin "2") (pinfunction "2_2") (pintype "passive"))
    )
    (net (code "121") (name "unconnected-(JP51-Pad1)") (class "Default")
      (node (ref "JP51") (pin "1") (pinfunction "1_1") (pintype "passive"))
    )
    (net (code "122") (name "unconnected-(JP51-Pad2)") (class "Default")
      (node (ref "JP51") (pin "2") (pinfunction "2_2") (pintype "passive"))
    )
    (net (code "123") (name "unconnected-(JP52-Pad1)") (class "Default")
      (node (ref "JP52") (pin "1") (pinfunction "1_1") (pintype "passive"))
    )
    (net (code "124") (name "unconnected-(JP52-Pad2)") (class "Default")
      (node (ref "JP52") (pin "2") (pinfunction "2_2") (pintype "passive"))
    )
    (net (code "125") (name "unconnected-(JP53-Pad1)") (class "Default")
      (node (ref "JP53") (pin "1") (pinfunction "1_1") (pintype "passive"))
    )
    (net (code "126") (name "unconnected-(JP53-Pad2)") (class "Default")
      (node (ref "JP53") (pin "2") (pinfunction "2_2") (pintype "passive"))
    )
    (net (code "127") (name "unconnected-(JP54-Pad1)") (class "Default")
      (node (ref "JP54") (pin "1") (pinfunction "1_1") (pintype "passive"))
    )
    (net (code "128") (name "unconnected-(JP54-Pad2)") (class "Default")
      (node (ref "JP54") (pin "2") (pinfunction "2_2") (pintype "passive"))
    )
    (net (code "129") (name "unconnected-(JP55-Pad1)") (class "Default")
      (node (ref "JP55") (pin "1") (pinfunction "1_1") (pintype "passive"))
    )
    (net (code "130") (name "unconnected-(JP55-Pad2)") (class "Default")
      (node (ref "JP55") (pin "2") (pinfunction "2_2") (pintype "passive"))
    )
    (net (code "131") (name "unconnected-(JP56-Pad1)") (class "Default")
      (node (ref "JP56") (pin "1") (pinfunction "1_1") (pintype "passive"))
    )
    (net (code "132") (name "unconnected-(JP56-Pad2)") (class "Default")
      (node (ref "JP56") (pin "2") (pinfunction "2_2") (pintype "passive"))
    )
    (net (code "133") (name "unconnected-(JP57-Pad1)") (class "Default")
      (node (ref "JP57") (pin "1") (pinfunction "1_1") (pintype "passive"))
    )
    (net (code "134") (name "unconnected-(JP57-Pad2)") (class "Default")
      (node (ref "JP57") (pin "2") (pinfunction "2_2") (pintype "passive"))
    )
    (net (code "135") (name "unconnected-(JP58-Pad1)") (class "Default")
      (node (ref "JP58") (pin "1") (pinfunction "1_1") (pintype "passive"))
    )
    (net (code "136") (name "unconnected-(JP58-Pad2)") (class "Default")
      (node (ref "JP58") (pin "2") (pinfunction "2_2") (pintype "passive"))
    )
    (net (code "137") (name "unconnected-(JP59-Pad1)") (class "Default")
      (node (ref "JP59") (pin "1") (pinfunction "1_1") (pintype "passive"))
    )
    (net (code "138") (name "unconnected-(JP59-Pad2)") (class "Default")
      (node (ref "JP59") (pin "2") (pinfunction "2_2") (pintype "passive"))
    )
    (net (code "139") (name "unconnected-(JP60-Pad1)") (class "Default")
      (node (ref "JP60") (pin "1") (pinfunction "1_1") (pintype "passive"))
    )
    (net (code "140") (name "unconnected-(JP60-Pad2)") (class "Default")
      (node (ref "JP60") (pin "2") (pinfunction "2_2") (pintype "passive"))
    )
    (net (code "141") (name "unconnected-(JP61-Pad1)") (class "Default")
      (node (ref "JP61") (pin "1") (pinfunction "1_1") (pintype "passive"))
    )
    (net (code "142") (name "unconnected-(JP61-Pad2)") (class "Default")
      (node (ref "JP61") (pin "2") (pinfunction "2_2") (pintype "passive"))
    )
    (net (code "143") (name "unconnected-(JP62-Pad1)") (class "Default")
      (node (ref "JP62") (pin "1") (pinfunction "1_1") (pintype "passive"))
    )
    (net (code "144") (name "unconnected-(JP62-Pad2)") (class "Default")
      (node (ref "JP62") (pin "2") (pinfunction "2_2") (pintype "passive"))
    )
    (net (code "145") (name "unconnected-(JP63-Pad1)") (class "Default")
      (node (ref "JP63") (pin "1") (pinfunction "1_1") (pintype "passive"))
    )
    (net (code "146") (name "unconnected-(JP63-Pad2)") (class "Default")
      (node (ref "JP63") (pin "2") (pinfunction "2_2") (pintype "passive"))
    )
    (net (code "147") (name "unconnected-(JP64-Pad1)") (class "Default")
      (node (ref "JP64") (pin "1") (pinfunction "1_1") (pintype "passive"))
    )
    (net (code "148") (name "unconnected-(JP64-Pad2)") (class "Default")
      (node (ref "JP64") (pin "2") (pinfunction "2_2") (pintype "passive"))
    )
    (net (code "149") (name "unconnected-(JP65-Pad1)") (class "Default")
      (node (ref "JP65") (pin "1") (pinfunction "1_1") (pintype "passive"))
    )
    (net (code "150") (name "unconnected-(JP65-Pad2)") (class "Default")
      (node (ref "JP65") (pin "2") (pinfunction "2_2") (pintype "passive"))
    )
    (net (code "151") (name "unconnected-(JP66-Pad1)") (class "Default")
      (node (ref "JP66") (pin "1") (pinfunction "1_1") (pintype "passive"))
    )
    (net (code "152") (name "unconnected-(JP66-Pad2)") (class "Default")
      (node (ref "JP66") (pin "2") (pinfunction "2_2") (pintype "passive"))
    )
    (net (code "153") (name "unconnected-(JP67-Pad1)") (class "Default")
      (node (ref "JP67") (pin "1") (pinfunction "1_1") (pintype "passive"))
    )
    (net (code "154") (name "unconnected-(JP67-Pad2)") (class "Default")
      (node (ref "JP67") (pin "2") (pinfunction "2_2") (pintype "passive"))
    )
    (net (code "155") (name "unconnected-(JP68-Pad1)") (class "Default")
      (node (ref "JP68") (pin "1") (pinfunction "1_1") (pintype "passive"))
    )
    (net (code "156") (name "unconnected-(JP68-Pad2)") (class "Default")
      (node (ref "JP68") (pin "2") (pinfunction "2_2") (pintype "passive"))
    )
    (net (code "157") (name "unconnected-(JP69-Pad1)") (class "Default")
      (node (ref "JP69") (pin "1") (pinfunction "1_1") (pintype "passive"))
    )
    (net (code "158") (name "unconnected-(JP69-Pad2)") (class "Default")
      (node (ref "JP69") (pin "2") (pinfunction "2_2") (pintype "passive"))
    )
    (net (code "159") (name "unconnected-(JP70-Pad1)") (class "Default")
      (node (ref "JP70") (pin "1") (pinfunction "1_1") (pintype "passive"))
    )
    (net (code "160") (name "unconnected-(JP70-Pad2)") (class "Default")
      (node (ref "JP70") (pin "2") (pinfunction "2_2") (pintype "passive"))
    )
    (net (code "161") (name "unconnected-(JP71-Pad1)") (class "Default")
      (node (ref "JP71") (pin "1") (pinfunction "1_1") (pintype "passive"))
    )
    (net (code "162") (name "unconnected-(JP71-Pad2)") (class "Default")
      (node (ref "JP71") (pin "2") (pinfunction "2_2") (pintype "passive"))
    )
    (net (code "163") (name "unconnected-(JP72-Pad1)") (class "Default")
      (node (ref "JP72") (pin "1") (pinfunction "1_1") (pintype "passive"))
    )
    (net (code "164") (name "unconnected-(JP72-Pad2)") (class "Default")
      (node (ref "JP72") (pin "2") (pinfunction "2_2") (pintype "passive"))
    )
    (net (code "165") (name "unconnected-(JP73-Pad1)") (class "Default")
      (node (ref "JP73") (pin "1") (pinfunction "1_1") (pintype "passive"))
    )
    (net (code "166") (name "unconnected-(JP73-Pad2)") (class "Default")
      (node (ref "JP73") (pin "2") (pinfunction "2_2") (pintype "passive"))
    )
    (net (code "167") (name "unconnected-(JP74-Pad1)") (class "Default")
      (node (ref "JP74") (pin "1") (pinfunction "1_1") (pintype "passive"))
    )
    (net (code "168") (name "unconnected-(JP74-Pad2)") (class "Default")
      (node (ref "JP74") (pin "2") (pinfunction "2_2") (pintype "passive"))
    )
    (net (code "169") (name "unconnected-(JP75-Pad1)") (class "Default")
      (node (ref "JP75") (pin "1") (pinfunction "1_1") (pintype "passive"))
    )
    (net (code "170") (name "unconnected-(JP75-Pad2)") (class "Default")
      (node (ref "JP75") (pin "2") (pinfunction "2_2") (pintype "passive"))
    )
    (net (code "171") (name "unconnected-(JP76-Pad1)") (class "Default")
      (node (ref "JP76") (pin "1") (pinfunction "1_1") (pintype "passive"))
    )
    (net (code "172") (name "unconnected-(JP76-Pad2)") (class "Default")
      (node (ref "JP76") (pin "2") (pinfunction "2_2") (pintype "passive"))
    )
    (net (code "173") (name "unconnected-(JP77-Pad1)") (class "Default")
      (node (ref "JP77") (pin "1") (pinfunction "1_1") (pintype "passive"))
    )
    (net (code "174") (name "unconnected-(JP77-Pad2)") (class "Default")
      (node (ref "JP77") (pin "2") (pinfunction "2_2") (pintype "passive"))
    )
    (net (code "175") (name "unconnected-(JP78-Pad1)") (class "Default")
      (node (ref "JP78") (pin "1") (pinfunction "1_1") (pintype "passive"))
    )
    (net (code "176") (name "unconnected-(JP78-Pad2)") (class "Default")
      (node (ref "JP78") (pin "2") (pinfunction "2_2") (pintype "passive"))
    )
    (net (code "177") (name "unconnected-(JP79-Pad1)") (class "Default")
      (node (ref "JP79") (pin "1") (pinfunction "1_1") (pintype "passive"))
    )
    (net (code "178") (name "unconnected-(JP79-Pad2)") (class "Default")
      (node (ref "JP79") (pin "2") (pinfunction "2_2") (pintype "passive"))
    )
    (net (code "179") (name "unconnected-(JP80-Pad1)") (class "Default")
      (node (ref "JP80") (pin "1") (pinfunction "1_1") (pintype "passive"))
    )
    (net (code "180") (name "unconnected-(JP80-Pad2)") (class "Default")
      (node (ref "JP80") (pin "2") (pinfunction "2_2") (pintype "passive"))
    )
    (net (code "181") (name "unconnected-(JP81-Pad1)") (class "Default")
      (node (ref "JP81") (pin "1") (pinfunction "1_1") (pintype "passive"))
    )
    (net (code "182") (name "unconnected-(JP81-Pad2)") (class "Default")
      (node (ref "JP81") (pin "2") (pinfunction "2_2") (pintype "passive"))
    )
    (net (code "183") (name "unconnected-(JP82-Pad1)") (class "Default")
      (node (ref "JP82") (pin "1") (pinfunction "1_1") (pintype "passive"))
    )
    (net (code "184") (name "unconnected-(JP82-Pad2)") (class "Default")
      (node (ref "JP82") (pin "2") (pinfunction "2_2") (pintype "passive"))
    )
    (net (code "185") (name "unconnected-(JP83-Pad1)") (class "Default")
      (node (ref "JP83") (pin "1") (pinfunction "1_1") (pintype "passive"))
    )
    (net (code "186") (name "unconnected-(JP83-Pad2)") (class "Default")
      (node (ref "JP83") (pin "2") (pinfunction "2_2") (pintype "passive"))
    )
    (net (code "187") (name "unconnected-(JP84-Pad1)") (class "Default")
      (node (ref "JP84") (pin "1") (pinfunction "1_1") (pintype "passive"))
    )
    (net (code "188") (name "unconnected-(JP84-Pad2)") (class "Default")
      (node (ref "JP84") (pin "2") (pinfunction "2_2") (pintype "passive"))
    )
  )
)
